# PCB-GONIO-V1.net
KiCad netlist of a schematic drawn in EAGLE
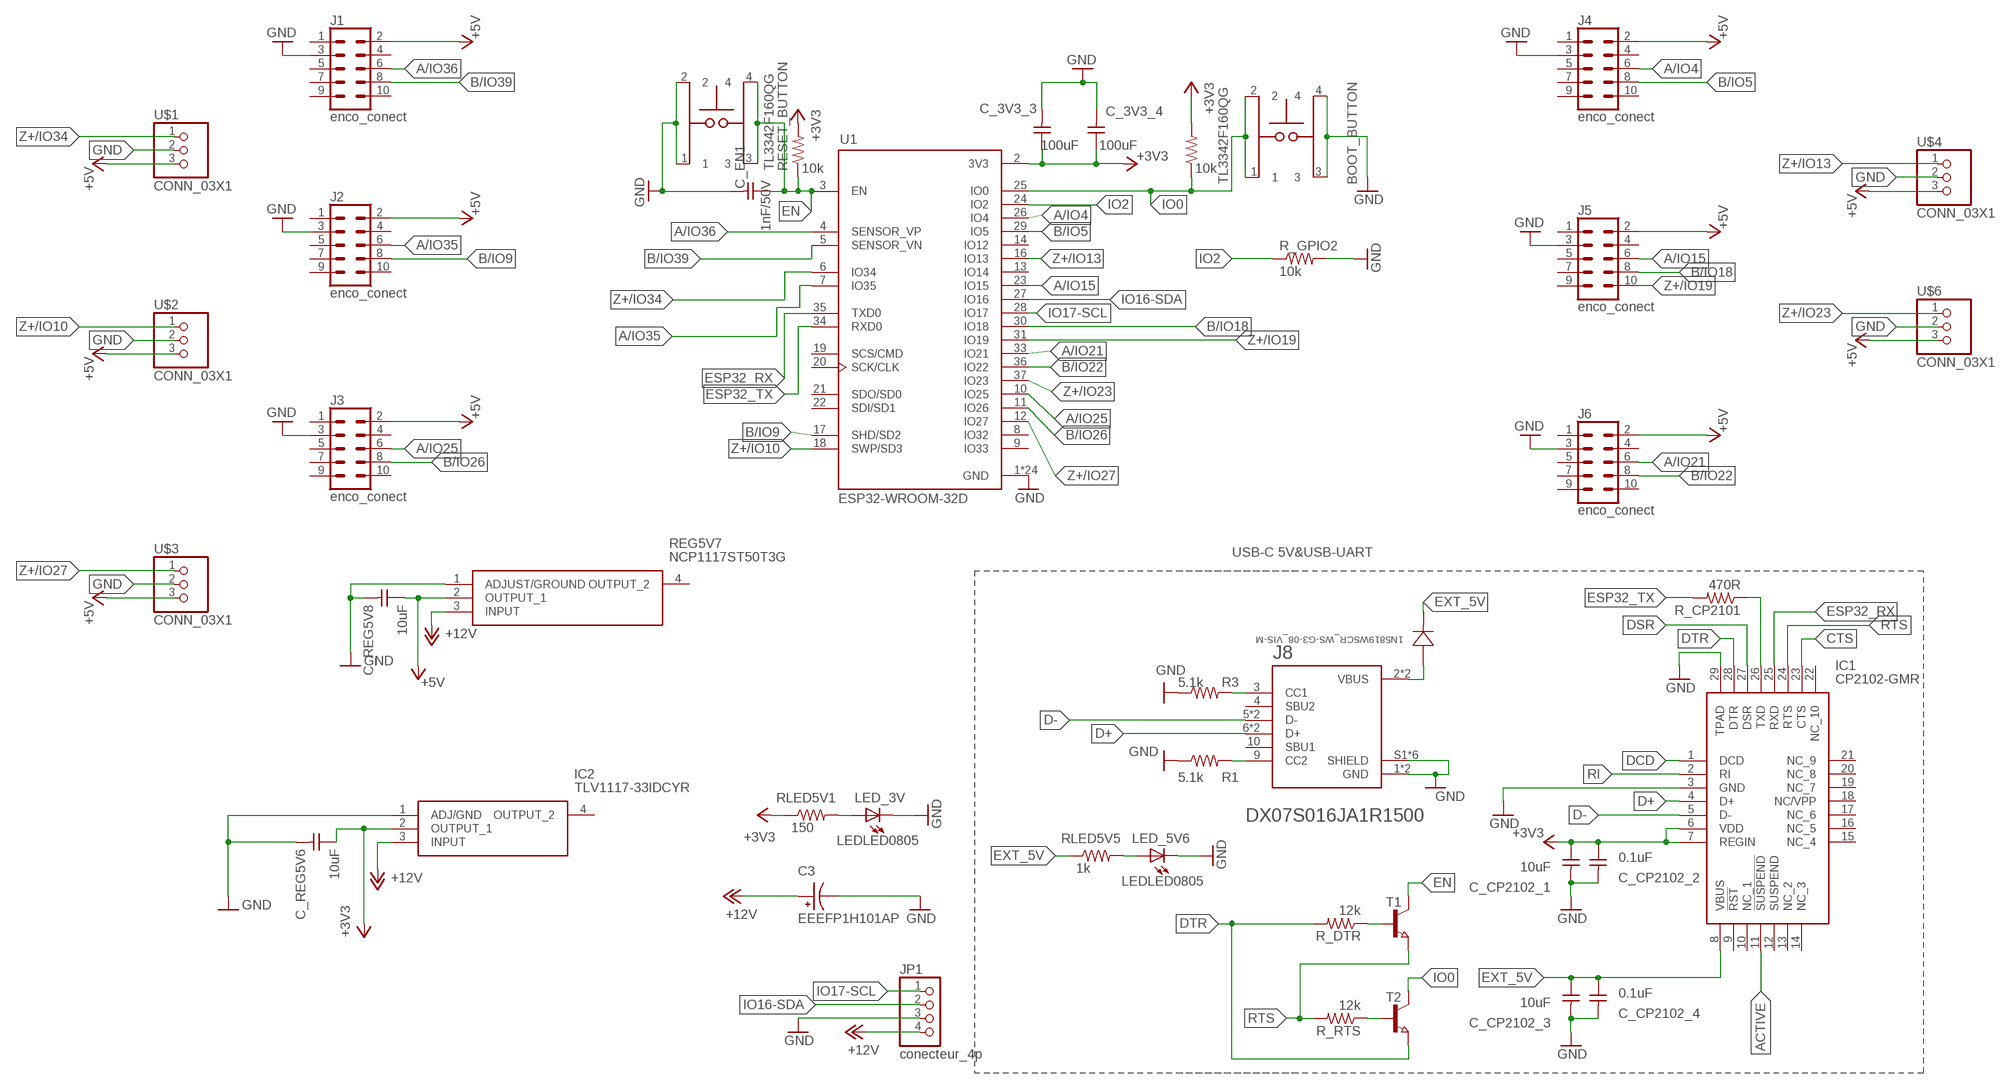
[diagram p0: schematic, sheet 1]

(export (version "E")
  (design (tool "Eeschema 10.0.6"))
  (components
    (comp (ref "BOOT_BUTTON")
      (value "TL3342F160QG")
      (footprint "eagle-import:SW_TL3342F160QG")
      (fields (field (name "MF") "E-Switch"))
      (libsource (lib "eagle-import") (part "TL3342F160QG"))
    )
    (comp (ref "C3")
      (value "EEEFP1H101AP")
      (footprint "eagle-import:CAP_EEEFP1H101AP")
      (fields (field (name "DIGIKEY_PART_NUMBER") "P19726TR-ND") (field (name "MF") "Panasonic"))
      (libsource (lib "eagle-import") (part "EEEFP1H101AP"))
    )
    (comp (ref "CR1")
      (value "1N5819WSCR_WS-G3-08_VIS-M")
      (footprint "eagle-import:CR_WS-G3-08_VIS-M")
      (fields
        (field (name "MANUFACTURER_PART_NUMBER") "1N4148WS-G3-08")
        (field (name "COPYRIGHT") "Copyright (C) 2022 Ultra Librarian. All rights reserved.")
      )
      (libsource (lib "eagle-import") (part "1N5819WSCR_WS-G3-08_VIS-M"))
    )
    (comp (ref "C_3V3_3")
      (value "100uF")
      (footprint "eagle-import:C1206FAB")
      (libsource (lib "eagle-import") (part "CAP_UNPOLARIZEDFAB"))
    )
    (comp (ref "C_3V3_4")
      (value "100uF")
      (footprint "eagle-import:C1206FAB")
      (libsource (lib "eagle-import") (part "CAP_UNPOLARIZEDFAB"))
    )
    (comp (ref "C_CP2102_1")
      (value "10uF")
      (footprint "eagle-import:C1206FAB")
      (libsource (lib "eagle-import") (part "CAP_UNPOLARIZEDFAB"))
    )
    (comp (ref "C_CP2102_2")
      (value "0.1uF")
      (footprint "eagle-import:C1206FAB")
      (libsource (lib "eagle-import") (part "CAP_UNPOLARIZEDFAB"))
    )
    (comp (ref "C_CP2102_3")
      (value "10uF")
      (footprint "eagle-import:C1206FAB")
      (libsource (lib "eagle-import") (part "CAP_UNPOLARIZEDFAB"))
    )
    (comp (ref "C_CP2102_4")
      (value "0.1uF")
      (footprint "eagle-import:C1206FAB")
      (libsource (lib "eagle-import") (part "CAP_UNPOLARIZEDFAB"))
    )
    (comp (ref "C_EN1")
      (value "1nF/50V")
      (footprint "eagle-import:C1206FAB")
      (libsource (lib "eagle-import") (part "CAP_UNPOLARIZEDFAB"))
    )
    (comp (ref "C_REG5V6")
      (value "10uF")
      (footprint "eagle-import:C1206FAB")
      (libsource (lib "eagle-import") (part "CAP_UNPOLARIZEDFAB"))
    )
    (comp (ref "C_REG5V8")
      (value "10uF")
      (footprint "eagle-import:C1206FAB")
      (libsource (lib "eagle-import") (part "CAP_UNPOLARIZEDFAB"))
    )
    (comp (ref "IC1")
      (value "CP2102-GMR")
      (footprint "eagle-import:QFN50P500X500X100-29N")
      (fields (field (name "MOUSER_PART_NUMBER") "634-CP2102-GMR"))
      (libsource (lib "eagle-import") (part "CP2102-GMR"))
    )
    (comp (ref "IC2")
      (value "TLV1117-33IDCYR")
      (footprint "eagle-import:SOT230P700X180-4N")
      (fields (field (name "MOUSER_PART_NUMBER") "595-TLV1117-33IDCYR"))
      (libsource (lib "eagle-import") (part "TLV1117-33IDCYR"))
    )
    (comp (ref "J1")
      (value "enco_conect")
      (footprint "eagle-import:2X5-SHROUDED")
      (libsource (lib "eagle-import") (part "CONN_05X2SHD"))
    )
    (comp (ref "J2")
      (value "enco_conect")
      (footprint "eagle-import:2X5-SHROUDED")
      (libsource (lib "eagle-import") (part "CONN_05X2SHD"))
    )
    (comp (ref "J3")
      (value "enco_conect")
      (footprint "eagle-import:2X5-SHROUDED")
      (libsource (lib "eagle-import") (part "CONN_05X2SHD"))
    )
    (comp (ref "J4")
      (value "enco_conect")
      (footprint "eagle-import:2X5-SHROUDED")
      (libsource (lib "eagle-import") (part "CONN_05X2SHD"))
    )
    (comp (ref "J5")
      (value "enco_conect")
      (footprint "eagle-import:2X5-SHROUDED")
      (libsource (lib "eagle-import") (part "CONN_05X2SHD"))
    )
    (comp (ref "J6")
      (value "enco_conect")
      (footprint "eagle-import:2X5-SHROUDED")
      (libsource (lib "eagle-import") (part "CONN_05X2SHD"))
    )
    (comp (ref "J8")
      (value "DX07S016JA1R1500")
      (footprint "eagle-import:JAE_DX07S016JA1R1500")
      (fields (field (name "MF") "Japan Aviation Electronics"))
      (libsource (lib "eagle-import") (part "DX07S016JA1R1500"))
    )
    (comp (ref "JP1")
      (value "conecteur_4p")
      (footprint "eagle-import:1X04")
      (libsource (lib "eagle-import") (part "PINHD-1X4"))
    )
    (comp (ref "LED_3V")
      (value "LEDLED0805")
      (footprint "eagle-import:LEDC2012X90N")
      (libsource (lib "eagle-import") (part "LEDLED0805"))
    )
    (comp (ref "LED_5V6")
      (value "LEDLED0805")
      (footprint "eagle-import:LEDC2012X90N")
      (libsource (lib "eagle-import") (part "LEDLED0805"))
    )
    (comp (ref "R1")
      (value "5.1k")
      (footprint "eagle-import:R1206W")
      (libsource (lib "eagle-import") (part "R-US_R1206W"))
    )
    (comp (ref "R3")
      (value "5.1k")
      (footprint "eagle-import:R1206W")
      (libsource (lib "eagle-import") (part "R-US_R1206W"))
    )
    (comp (ref "REG5V7")
      (value "NCP1117ST50T3G")
      (footprint "eagle-import:SOT230P700X180-4N")
      (fields (field (name "LCSC_PART") "C17314") (field (name "RS_PART_NUMBER") "8022130P"))
      (libsource (lib "eagle-import") (part "NCP1117ST50T3G"))
    )
    (comp (ref "RESET_BUTTON")
      (value "TL3342F160QG")
      (footprint "eagle-import:SW_TL3342F160QG")
      (fields (field (name "MF") "E-Switch"))
      (libsource (lib "eagle-import") (part "TL3342F160QG"))
    )
    (comp (ref "RLED5V1")
      (value "150")
      (footprint "eagle-import:R1206FAB")
      (libsource (lib "eagle-import") (part "R1206FAB"))
    )
    (comp (ref "RLED5V5")
      (value "1k")
      (footprint "eagle-import:R1206FAB")
      (libsource (lib "eagle-import") (part "R1206FAB"))
    )
    (comp (ref "R_CP2101")
      (value "470R")
      (footprint "eagle-import:R1206FAB")
      (libsource (lib "eagle-import") (part "R1206FAB"))
    )
    (comp (ref "R_DTR")
      (value "12k")
      (footprint "eagle-import:R1206FAB")
      (libsource (lib "eagle-import") (part "R1206FAB"))
    )
    (comp (ref "R_GPIO2")
      (value "10k")
      (footprint "eagle-import:R1206FAB")
      (libsource (lib "eagle-import") (part "R1206FAB"))
    )
    (comp (ref "R_PULL_UP1")
      (value "10k")
      (footprint "eagle-import:R1206FAB")
      (libsource (lib "eagle-import") (part "R1206FAB"))
    )
    (comp (ref "R_PULL_UP3")
      (value "10k")
      (footprint "eagle-import:R1206FAB")
      (libsource (lib "eagle-import") (part "R1206FAB"))
    )
    (comp (ref "R_RTS")
      (value "12k")
      (footprint "eagle-import:R1206FAB")
      (libsource (lib "eagle-import") (part "R1206FAB"))
    )
    (comp (ref "T1")
      (value "T_NPN_S8050-J3Y_CHANGJ_SOT23-BEC")
      (footprint "eagle-import:SOT23")
      (fields (field (name "LCSC_PART") "C2146"))
      (libsource (lib "eagle-import") (part "T_NPN__SOT23-BECS8050-J3Y_CHANGJ"))
    )
    (comp (ref "T2")
      (value "T_NPN_S8050-J3Y_CHANGJ_SOT23-BEC")
      (footprint "eagle-import:SOT23")
      (fields (field (name "LCSC_PART") "C2146"))
      (libsource (lib "eagle-import") (part "T_NPN__SOT23-BECS8050-J3Y_CHANGJ"))
    )
    (comp (ref "U$1")
      (value "CONN_03X1")
      (footprint "eagle-import:1X3")
      (libsource (lib "eagle-import") (part "CONN_03X1"))
    )
    (comp (ref "U$2")
      (value "CONN_03X1")
      (footprint "eagle-import:1X3")
      (libsource (lib "eagle-import") (part "CONN_03X1"))
    )
    (comp (ref "U$3")
      (value "CONN_03X1")
      (footprint "eagle-import:1X3")
      (libsource (lib "eagle-import") (part "CONN_03X1"))
    )
    (comp (ref "U$4")
      (value "CONN_03X1")
      (footprint "eagle-import:1X3")
      (libsource (lib "eagle-import") (part "CONN_03X1"))
    )
    (comp (ref "U$6")
      (value "CONN_03X1")
      (footprint "eagle-import:1X3")
      (libsource (lib "eagle-import") (part "CONN_03X1"))
    )
    (comp (ref "U1")
      (value "ESP32-WROOM-32D")
      (footprint "eagle-import:MODULE_ESP32-WROOM-32D")
      (fields (field (name "MF") "Espressif Systems"))
      (libsource (lib "eagle-import") (part "ESP32-WROOM-32D"))
    )
  )
  (nets
    (net (code "1") (name "+3V3") (class "Default")
      (node (ref "C_3V3_3") (pin "1") (pinfunction "1_1") (pintype "passive"))
      (node (ref "C_3V3_4") (pin "1") (pinfunction "1_1") (pintype "passive"))
      (node (ref "C_CP2102_1") (pin "1") (pinfunction "1_1") (pintype "passive"))
      (node (ref "C_CP2102_2") (pin "1") (pinfunction "1_1") (pintype "passive"))
      (node (ref "C_REG5V6") (pin "1") (pinfunction "1_1") (pintype "passive"))
      (node (ref "IC1") (pin "6") (pinfunction "VDD_6") (pintype "bidirectional"))
      (node (ref "IC1") (pin "7") (pinfunction "REGIN_7") (pintype "bidirectional"))
      (node (ref "IC2") (pin "2") (pinfunction "OUTPUT_1_2") (pintype "bidirectional"))
      (node (ref "RLED5V1") (pin "1") (pinfunction "1_1") (pintype "passive"))
      (node (ref "R_PULL_UP1") (pin "2") (pinfunction "2_2") (pintype "passive"))
      (node (ref "R_PULL_UP3") (pin "2") (pinfunction "2_2") (pintype "passive"))
      (node (ref "U1") (pin "2") (pinfunction "3V3_2") (pintype "power_in"))
    )
    (net (code "2") (name "+5V") (class "Default")
      (node (ref "C_REG5V8") (pin "1") (pinfunction "1_1") (pintype "passive"))
      (node (ref "J1") (pin "2") (pinfunction "2_2") (pintype "passive"))
      (node (ref "J2") (pin "2") (pinfunction "2_2") (pintype "passive"))
      (node (ref "J3") (pin "2") (pinfunction "2_2") (pintype "passive"))
      (node (ref "J4") (pin "2") (pinfunction "2_2") (pintype "passive"))
      (node (ref "J5") (pin "2") (pinfunction "2_2") (pintype "passive"))
      (node (ref "J6") (pin "2") (pinfunction "2_2") (pintype "passive"))
      (node (ref "REG5V7") (pin "2") (pinfunction "OUTPUT_1_2") (pintype "bidirectional"))
      (node (ref "U$1") (pin "3") (pinfunction "3_3") (pintype "passive"))
      (node (ref "U$2") (pin "3") (pinfunction "3_3") (pintype "passive"))
      (node (ref "U$3") (pin "3") (pinfunction "3_3") (pintype "passive"))
      (node (ref "U$4") (pin "3") (pinfunction "3_3") (pintype "passive"))
      (node (ref "U$6") (pin "3") (pinfunction "3_3") (pintype "passive"))
    )
    (net (code "3") (name "+12V") (class "Default")
      (node (ref "C3") (pin "1") (pinfunction "1_1") (pintype "passive"))
      (node (ref "IC2") (pin "3") (pinfunction "INPUT_3") (pintype "bidirectional"))
      (node (ref "JP1") (pin "4") (pinfunction "4_4") (pintype "passive"))
      (node (ref "REG5V7") (pin "3") (pinfunction "INPUT_3") (pintype "bidirectional"))
    )
    (net (code "4") (name "ACTIVE") (class "Default")
      (node (ref "IC1") (pin "11") (pinfunction "~{SUSPEND}_11") (pintype "bidirectional"))
    )
    (net (code "5") (name "A{slash}IO4") (class "Default")
      (node (ref "J4") (pin "6") (pinfunction "6_6") (pintype "passive"))
      (node (ref "U1") (pin "26") (pinfunction "IO4_26") (pintype "bidirectional"))
    )
    (net (code "6") (name "A{slash}IO15") (class "Default")
      (node (ref "J5") (pin "6") (pinfunction "6_6") (pintype "passive"))
      (node (ref "U1") (pin "23") (pinfunction "IO15_23") (pintype "bidirectional"))
    )
    (net (code "7") (name "A{slash}IO21") (class "Default")
      (node (ref "J6") (pin "6") (pinfunction "6_6") (pintype "passive"))
      (node (ref "U1") (pin "33") (pinfunction "IO21_33") (pintype "bidirectional"))
    )
    (net (code "8") (name "A{slash}IO25") (class "Default")
      (node (ref "J3") (pin "6") (pinfunction "6_6") (pintype "passive"))
      (node (ref "U1") (pin "10") (pinfunction "IO25_10") (pintype "bidirectional"))
    )
    (net (code "9") (name "A{slash}IO35") (class "Default")
      (node (ref "J2") (pin "6") (pinfunction "6_6") (pintype "passive"))
      (node (ref "U1") (pin "7") (pinfunction "IO35_7") (pintype "input"))
    )
    (net (code "10") (name "A{slash}IO36") (class "Default")
      (node (ref "J1") (pin "6") (pinfunction "6_6") (pintype "passive"))
      (node (ref "U1") (pin "4") (pinfunction "SENSOR_VP_4") (pintype "input"))
    )
    (net (code "11") (name "B{slash}IO5") (class "Default")
      (node (ref "J4") (pin "8") (pinfunction "8_8") (pintype "passive"))
      (node (ref "U1") (pin "29") (pinfunction "IO5_29") (pintype "bidirectional"))
    )
    (net (code "12") (name "B{slash}IO9") (class "Default")
      (node (ref "J2") (pin "8") (pinfunction "8_8") (pintype "passive"))
      (node (ref "U1") (pin "17") (pinfunction "SHD/SD2_17") (pintype "bidirectional"))
    )
    (net (code "13") (name "B{slash}IO18") (class "Default")
      (node (ref "J5") (pin "8") (pinfunction "8_8") (pintype "passive"))
      (node (ref "U1") (pin "30") (pinfunction "IO18_30") (pintype "bidirectional"))
    )
    (net (code "14") (name "B{slash}IO22") (class "Default")
      (node (ref "J6") (pin "8") (pinfunction "8_8") (pintype "passive"))
      (node (ref "U1") (pin "36") (pinfunction "IO22_36") (pintype "bidirectional"))
    )
    (net (code "15") (name "B{slash}IO26") (class "Default")
      (node (ref "J3") (pin "8") (pinfunction "8_8") (pintype "passive"))
      (node (ref "U1") (pin "11") (pinfunction "IO26_11") (pintype "bidirectional"))
    )
    (net (code "16") (name "B{slash}IO39") (class "Default")
      (node (ref "J1") (pin "8") (pinfunction "8_8") (pintype "passive"))
      (node (ref "U1") (pin "5") (pinfunction "SENSOR_VN_5") (pintype "input"))
    )
    (net (code "17") (name "CTS") (class "Default")
      (node (ref "IC1") (pin "23") (pinfunction "CTS_23") (pintype "bidirectional"))
    )
    (net (code "18") (name "D+") (class "Default")
      (node (ref "IC1") (pin "4") (pinfunction "D+_4") (pintype "bidirectional"))
      (node (ref "J8") (pin "6") (pinfunction "D+_6") (pintype "passive"))
      (node (ref "J8") (pin "7") (pinfunction "D+_7") (pintype "passive"))
    )
    (net (code "19") (name "D-") (class "Default")
      (node (ref "IC1") (pin "5") (pinfunction "D-_5") (pintype "bidirectional"))
      (node (ref "J8") (pin "5") (pinfunction "D-_5") (pintype "passive"))
      (node (ref "J8") (pin "8") (pinfunction "D-_8") (pintype "passive"))
    )
    (net (code "20") (name "DCD") (class "Default")
      (node (ref "IC1") (pin "1") (pinfunction "DCD_1") (pintype "bidirectional"))
    )
    (net (code "21") (name "DSR") (class "Default")
      (node (ref "IC1") (pin "27") (pinfunction "DSR_27") (pintype "bidirectional"))
    )
    (net (code "22") (name "DTR") (class "Default")
      (node (ref "IC1") (pin "28") (pinfunction "DTR_28") (pintype "bidirectional"))
      (node (ref "R_DTR") (pin "2") (pinfunction "2_2") (pintype "passive"))
      (node (ref "T2") (pin "2") (pinfunction "E_2") (pintype "passive"))
    )
    (net (code "23") (name "EN") (class "Default")
      (node (ref "C_EN1") (pin "1") (pinfunction "1_1") (pintype "passive"))
      (node (ref "RESET_BUTTON") (pin "3") (pinfunction "3_3") (pintype "passive"))
      (node (ref "RESET_BUTTON") (pin "4") (pinfunction "4_4") (pintype "passive"))
      (node (ref "R_PULL_UP1") (pin "1") (pinfunction "1_1") (pintype "passive"))
      (node (ref "T1") (pin "3") (pinfunction "C_3") (pintype "passive"))
      (node (ref "U1") (pin "3") (pinfunction "EN_3") (pintype "input"))
    )
    (net (code "24") (name "ESP32_RX") (class "Default")
      (node (ref "IC1") (pin "25") (pinfunction "RXD_25") (pintype "bidirectional"))
      (node (ref "U1") (pin "35") (pinfunction "TXD0_35") (pintype "bidirectional"))
    )
    (net (code "25") (name "ESP32_TX") (class "Default")
      (node (ref "R_CP2101") (pin "2") (pinfunction "2_2") (pintype "passive"))
      (node (ref "U1") (pin "34") (pinfunction "RXD0_34") (pintype "bidirectional"))
    )
    (net (code "26") (name "EXT_5V") (class "Default")
      (node (ref "CR1") (pin "1") (pinfunction "1_1") (pintype "passive"))
      (node (ref "C_CP2102_3") (pin "1") (pinfunction "1_1") (pintype "passive"))
      (node (ref "C_CP2102_4") (pin "1") (pinfunction "1_1") (pintype "passive"))
      (node (ref "IC1") (pin "8") (pinfunction "VBUS_8") (pintype "bidirectional"))
      (node (ref "RLED5V5") (pin "1") (pinfunction "1_1") (pintype "passive"))
    )
    (net (code "27") (name "GND") (class "Default")
      (node (ref "BOOT_BUTTON") (pin "3") (pinfunction "3_3") (pintype "passive"))
      (node (ref "BOOT_BUTTON") (pin "4") (pinfunction "4_4") (pintype "passive"))
      (node (ref "C3") (pin "2") (pinfunction "2_2") (pintype "passive"))
      (node (ref "C_3V3_3") (pin "2") (pinfunction "2_2") (pintype "passive"))
      (node (ref "C_3V3_4") (pin "2") (pinfunction "2_2") (pintype "passive"))
      (node (ref "C_CP2102_1") (pin "2") (pinfunction "2_2") (pintype "passive"))
      (node (ref "C_CP2102_2") (pin "2") (pinfunction "2_2") (pintype "passive"))
      (node (ref "C_CP2102_3") (pin "2") (pinfunction "2_2") (pintype "passive"))
      (node (ref "C_CP2102_4") (pin "2") (pinfunction "2_2") (pintype "passive"))
      (node (ref "C_EN1") (pin "2") (pinfunction "2_2") (pintype "passive"))
      (node (ref "C_REG5V6") (pin "2") (pinfunction "2_2") (pintype "passive"))
      (node (ref "C_REG5V8") (pin "2") (pinfunction "2_2") (pintype "passive"))
      (node (ref "IC1") (pin "29") (pinfunction "TPAD_29") (pintype "bidirectional"))
      (node (ref "IC1") (pin "3") (pinfunction "GND_3") (pintype "bidirectional"))
      (node (ref "IC2") (pin "1") (pinfunction "ADJ/GND_1") (pintype "bidirectional"))
      (node (ref "J1") (pin "3") (pinfunction "3_3") (pintype "passive"))
      (node (ref "J2") (pin "3") (pinfunction "3_3") (pintype "passive"))
      (node (ref "J3") (pin "3") (pinfunction "3_3") (pintype "passive"))
      (node (ref "J4") (pin "3") (pinfunction "3_3") (pintype "passive"))
      (node (ref "J5") (pin "3") (pinfunction "3_3") (pintype "passive"))
      (node (ref "J6") (pin "3") (pinfunction "3_3") (pintype "passive"))
      (node (ref "J8") (pin "1") (pinfunction "GND_1") (pintype "power_in"))
      (node (ref "J8") (pin "12") (pinfunction "GND_12") (pintype "power_in"))
      (node (ref "J8") (pin "S1") (pinfunction "SHIELD_S1") (pintype "passive"))
      (node (ref "J8") (pin "S2") (pinfunction "SHIELD_S2") (pintype "passive"))
      (node (ref "J8") (pin "S3") (pinfunction "SHIELD_S3") (pintype "passive"))
      (node (ref "J8") (pin "S4") (pinfunction "SHIELD_S4") (pintype "passive"))
      (node (ref "J8") (pin "S5") (pinfunction "SHIELD_S5") (pintype "passive"))
      (node (ref "J8") (pin "S6") (pinfunction "SHIELD_S6") (pintype "passive"))
      (node (ref "JP1") (pin "3") (pinfunction "3_3") (pintype "passive"))
      (node (ref "LED_3V") (pin "1") (pinfunction "C_1") (pintype "passive"))
      (node (ref "LED_5V6") (pin "1") (pinfunction "C_1") (pintype "passive"))
      (node (ref "R1") (pin "1") (pinfunction "1_1") (pintype "passive"))
      (node (ref "R3") (pin "1") (pinfunction "1_1") (pintype "passive"))
      (node (ref "REG5V7") (pin "1") (pinfunction "ADJUST/GROUND_1") (pintype "bidirectional"))
      (node (ref "RESET_BUTTON") (pin "1") (pinfunction "1_1") (pintype "passive"))
      (node (ref "RESET_BUTTON") (pin "2") (pinfunction "2_2") (pintype "passive"))
      (node (ref "R_GPIO2") (pin "2") (pinfunction "2_2") (pintype "passive"))
      (node (ref "U$1") (pin "2") (pinfunction "2_2") (pintype "passive"))
      (node (ref "U$2") (pin "2") (pinfunction "2_2") (pintype "passive"))
      (node (ref "U$3") (pin "2") (pinfunction "2_2") (pintype "passive"))
      (node (ref "U$4") (pin "2") (pinfunction "2_2") (pintype "passive"))
      (node (ref "U$6") (pin "2") (pinfunction "2_2") (pintype "passive"))
      (node (ref "U1") (pin "1") (pinfunction "GND_1") (pintype "power_in"))
      (node (ref "U1") (pin "15") (pinfunction "GND_15") (pintype "power_in"))
      (node (ref "U1") (pin "38") (pinfunction "GND_38") (pintype "power_in"))
      (node (ref "U1") (pin "39_1") (pinfunction "GND_39_1") (pintype "power_in"))
      (node (ref "U1") (pin "39_10") (pinfunction "GND_39_10") (pintype "power_in"))
      (node (ref "U1") (pin "39_11") (pinfunction "GND_39_11") (pintype "power_in"))
      (node (ref "U1") (pin "39_12") (pinfunction "GND_39_12") (pintype "power_in"))
      (node (ref "U1") (pin "39_13") (pinfunction "GND_39_13") (pintype "power_in"))
      (node (ref "U1") (pin "39_14") (pinfunction "GND_39_14") (pintype "power_in"))
      (node (ref "U1") (pin "39_15") (pinfunction "GND_39_15") (pintype "power_in"))
      (node (ref "U1") (pin "39_16") (pinfunction "GND_39_16") (pintype "power_in"))
      (node (ref "U1") (pin "39_17") (pinfunction "GND_39_17") (pintype "power_in"))
      (node (ref "U1") (pin "39_18") (pinfunction "GND_39_18") (pintype "power_in"))
      (node (ref "U1") (pin "39_19") (pinfunction "GND_39_19") (pintype "power_in"))
      (node (ref "U1") (pin "39_2") (pinfunction "GND_39_2") (pintype "power_in"))
      (node (ref "U1") (pin "39_20") (pinfunction "GND_39_20") (pintype "power_in"))
      (node (ref "U1") (pin "39_21") (pinfunction "GND_39_21") (pintype "power_in"))
      (node (ref "U1") (pin "39_3") (pinfunction "GND_39_3") (pintype "power_in"))
      (node (ref "U1") (pin "39_4") (pinfunction "GND_39_4") (pintype "power_in"))
      (node (ref "U1") (pin "39_5") (pinfunction "GND_39_5") (pintype "power_in"))
      (node (ref "U1") (pin "39_6") (pinfunction "GND_39_6") (pintype "power_in"))
      (node (ref "U1") (pin "39_7") (pinfunction "GND_39_7") (pintype "power_in"))
      (node (ref "U1") (pin "39_8") (pinfunction "GND_39_8") (pintype "power_in"))
      (node (ref "U1") (pin "39_9") (pinfunction "GND_39_9") (pintype "power_in"))
    )
    (net (code "28") (name "IO0") (class "Default")
      (node (ref "BOOT_BUTTON") (pin "1") (pinfunction "1_1") (pintype "passive"))
      (node (ref "BOOT_BUTTON") (pin "2") (pinfunction "2_2") (pintype "passive"))
      (node (ref "R_PULL_UP3") (pin "1") (pinfunction "1_1") (pintype "passive"))
      (node (ref "T2") (pin "3") (pinfunction "C_3") (pintype "passive"))
      (node (ref "U1") (pin "25") (pinfunction "IO0_25") (pintype "bidirectional"))
    )
    (net (code "29") (name "IO2") (class "Default")
      (node (ref "R_GPIO2") (pin "1") (pinfunction "1_1") (pintype "passive"))
      (node (ref "U1") (pin "24") (pinfunction "IO2_24") (pintype "bidirectional"))
    )
    (net (code "30") (name "IO16-SDA") (class "Default")
      (node (ref "JP1") (pin "2") (pinfunction "2_2") (pintype "passive"))
      (node (ref "U1") (pin "27") (pinfunction "IO16_27") (pintype "bidirectional"))
    )
    (net (code "31") (name "IO17-SCL") (class "Default")
      (node (ref "JP1") (pin "1") (pinfunction "1_1") (pintype "passive"))
      (node (ref "U1") (pin "28") (pinfunction "IO17_28") (pintype "bidirectional"))
    )
    (net (code "32") (name "Net-(CR1-Pad2)") (class "Default")
      (node (ref "CR1") (pin "2") (pinfunction "2_2") (pintype "passive"))
      (node (ref "J8") (pin "11") (pinfunction "VBUS_11") (pintype "power_in"))
      (node (ref "J8") (pin "2") (pinfunction "VBUS_2") (pintype "power_in"))
    )
    (net (code "33") (name "Net-(IC1-TXD)") (class "Default")
      (node (ref "IC1") (pin "26") (pinfunction "TXD_26") (pintype "bidirectional"))
      (node (ref "R_CP2101") (pin "1") (pinfunction "1_1") (pintype "passive"))
    )
    (net (code "34") (name "Net-(J8-CC1)") (class "Default")
      (node (ref "J8") (pin "3") (pinfunction "CC1_3") (pintype "passive"))
      (node (ref "R3") (pin "2") (pinfunction "2_2") (pintype "passive"))
    )
    (net (code "35") (name "Net-(J8-CC2)") (class "Default")
      (node (ref "J8") (pin "9") (pinfunction "CC2_9") (pintype "passive"))
      (node (ref "R1") (pin "2") (pinfunction "2_2") (pintype "passive"))
    )
    (net (code "36") (name "Net-(LED_3V-A)") (class "Default")
      (node (ref "LED_3V") (pin "2") (pinfunction "A_2") (pintype "passive"))
      (node (ref "RLED5V1") (pin "2") (pinfunction "2_2") (pintype "passive"))
    )
    (net (code "37") (name "Net-(LED_5V6-A)") (class "Default")
      (node (ref "LED_5V6") (pin "2") (pinfunction "A_2") (pintype "passive"))
      (node (ref "RLED5V5") (pin "2") (pinfunction "2_2") (pintype "passive"))
    )
    (net (code "38") (name "Net-(T1-B)") (class "Default")
      (node (ref "R_DTR") (pin "1") (pinfunction "1_1") (pintype "passive"))
      (node (ref "T1") (pin "1") (pinfunction "B_1") (pintype "passive"))
    )
    (net (code "39") (name "Net-(T2-B)") (class "Default")
      (node (ref "R_RTS") (pin "1") (pinfunction "1_1") (pintype "passive"))
      (node (ref "T2") (pin "1") (pinfunction "B_1") (pintype "passive"))
    )
    (net (code "40") (name "RI") (class "Default")
      (node (ref "IC1") (pin "2") (pinfunction "RI_2") (pintype "bidirectional"))
    )
    (net (code "41") (name "RTS") (class "Default")
      (node (ref "IC1") (pin "24") (pinfunction "RTS_24") (pintype "bidirectional"))
      (node (ref "R_RTS") (pin "2") (pinfunction "2_2") (pintype "passive"))
      (node (ref "T1") (pin "2") (pinfunction "E_2") (pintype "passive"))
    )
    (net (code "42") (name "Z+{slash}IO10") (class "Default")
      (node (ref "U$2") (pin "1") (pinfunction "1_1") (pintype "passive"))
      (node (ref "U1") (pin "18") (pinfunction "SWP/SD3_18") (pintype "bidirectional"))
    )
    (net (code "43") (name "Z+{slash}IO13") (class "Default")
      (node (ref "U$4") (pin "1") (pinfunction "1_1") (pintype "passive"))
      (node (ref "U1") (pin "16") (pinfunction "IO13_16") (pintype "bidirectional"))
    )
    (net (code "44") (name "Z+{slash}IO19") (class "Default")
      (node (ref "J5") (pin "10") (pinfunction "10_10") (pintype "passive"))
      (node (ref "U1") (pin "31") (pinfunction "IO19_31") (pintype "bidirectional"))
    )
    (net (code "45") (name "Z+{slash}IO23") (class "Default")
      (node (ref "U$6") (pin "1") (pinfunction "1_1") (pintype "passive"))
      (node (ref "U1") (pin "37") (pinfunction "IO23_37") (pintype "bidirectional"))
    )
    (net (code "46") (name "Z+{slash}IO27") (class "Default")
      (node (ref "U$3") (pin "1") (pinfunction "1_1") (pintype "passive"))
      (node (ref "U1") (pin "12") (pinfunction "IO27_12") (pintype "bidirectional"))
    )
    (net (code "47") (name "Z+{slash}IO34") (class "Default")
      (node (ref "U$1") (pin "1") (pinfunction "1_1") (pintype "passive"))
      (node (ref "U1") (pin "6") (pinfunction "IO34_6") (pintype "input"))
    )
    (net (code "48") (name "unconnected-(IC1-NC_1-Pad10)") (class "Default")
      (node (ref "IC1") (pin "10") (pinfunction "NC_1_10") (pintype "bidirectional"))
    )
    (net (code "49") (name "unconnected-(IC1-NC_2-Pad13)") (class "Default")
      (node (ref "IC1") (pin "13") (pinfunction "NC_2_13") (pintype "bidirectional"))
    )
    (net (code "50") (name "unconnected-(IC1-NC_3-Pad14)") (class "Default")
      (node (ref "IC1") (pin "14") (pinfunction "NC_3_14") (pintype "bidirectional"))
    )
    (net (code "51") (name "unconnected-(IC1-NC_4-Pad15)") (class "Default")
      (node (ref "IC1") (pin "15") (pinfunction "NC_4_15") (pintype "bidirectional"))
    )
    (net (code "52") (name "unconnected-(IC1-NC_5-Pad16)") (class "Default")
      (node (ref "IC1") (pin "16") (pinfunction "NC_5_16") (pintype "bidirectional"))
    )
    (net (code "53") (name "unconnected-(IC1-NC_6-Pad17)") (class "Default")
      (node (ref "IC1") (pin "17") (pinfunction "NC_6_17") (pintype "bidirectional"))
    )
    (net (code "54") (name "unconnected-(IC1-NC_7-Pad19)") (class "Default")
      (node (ref "IC1") (pin "19") (pinfunction "NC_7_19") (pintype "bidirectional"))
    )
    (net (code "55") (name "unconnected-(IC1-NC_8-Pad20)") (class "Default")
      (node (ref "IC1") (pin "20") (pinfunction "NC_8_20") (pintype "bidirectional"))
    )
    (net (code "56") (name "unconnected-(IC1-NC_9-Pad21)") (class "Default")
      (node (ref "IC1") (pin "21") (pinfunction "NC_9_21") (pintype "bidirectional"))
    )
    (net (code "57") (name "unconnected-(IC1-NC_10-Pad22)") (class "Default")
      (node (ref "IC1") (pin "22") (pinfunction "NC_10_22") (pintype "bidirectional"))
    )
    (net (code "58") (name "unconnected-(IC1-NC{slash}VPP-Pad18)") (class "Default")
      (node (ref "IC1") (pin "18") (pinfunction "NC/VPP_18") (pintype "bidirectional"))
    )
    (net (code "59") (name "unconnected-(IC1-SUSPEND-Pad12)") (class "Default")
      (node (ref "IC1") (pin "12") (pinfunction "SUSPEND_12") (pintype "bidirectional"))
    )
    (net (code "60") (name "unconnected-(IC1-~{RST}-Pad9)") (class "Default")
      (node (ref "IC1") (pin "9") (pinfunction "~{RST}_9") (pintype "bidirectional"))
    )
    (net (code "61") (name "unconnected-(IC2-OUTPUT_2-Pad4)") (class "Default")
      (node (ref "IC2") (pin "4") (pinfunction "OUTPUT_2_4") (pintype "bidirectional"))
    )
    (net (code "62") (name "unconnected-(J1-Pad1)") (class "Default")
      (node (ref "J1") (pin "1") (pinfunction "1_1") (pintype "passive"))
    )
    (net (code "63") (name "unconnected-(J1-Pad4)") (class "Default")
      (node (ref "J1") (pin "4") (pinfunction "4_4") (pintype "passive"))
    )
    (net (code "64") (name "unconnected-(J1-Pad5)") (class "Default")
      (node (ref "J1") (pin "5") (pinfunction "5_5") (pintype "passive"))
    )
    (net (code "65") (name "unconnected-(J1-Pad7)") (class "Default")
      (node (ref "J1") (pin "7") (pinfunction "7_7") (pintype "passive"))
    )
    (net (code "66") (name "unconnected-(J1-Pad9)") (class "Default")
      (node (ref "J1") (pin "9") (pinfunction "9_9") (pintype "passive"))
    )
    (net (code "67") (name "unconnected-(J1-Pad10)") (class "Default")
      (node (ref "J1") (pin "10") (pinfunction "10_10") (pintype "passive"))
    )
    (net (code "68") (name "unconnected-(J2-Pad1)") (class "Default")
      (node (ref "J2") (pin "1") (pinfunction "1_1") (pintype "passive"))
    )
    (net (code "69") (name "unconnected-(J2-Pad4)") (class "Default")
      (node (ref "J2") (pin "4") (pinfunction "4_4") (pintype "passive"))
    )
    (net (code "70") (name "unconnected-(J2-Pad5)") (class "Default")
      (node (ref "J2") (pin "5") (pinfunction "5_5") (pintype "passive"))
    )
    (net (code "71") (name "unconnected-(J2-Pad7)") (class "Default")
      (node (ref "J2") (pin "7") (pinfunction "7_7") (pintype "passive"))
    )
    (net (code "72") (name "unconnected-(J2-Pad9)") (class "Default")
      (node (ref "J2") (pin "9") (pinfunction "9_9") (pintype "passive"))
    )
    (net (code "73") (name "unconnected-(J2-Pad10)") (class "Default")
      (node (ref "J2") (pin "10") (pinfunction "10_10") (pintype "passive"))
    )
    (net (code "74") (name "unconnected-(J3-Pad1)") (class "Default")
      (node (ref "J3") (pin "1") (pinfunction "1_1") (pintype "passive"))
    )
    (net (code "75") (name "unconnected-(J3-Pad4)") (class "Default")
      (node (ref "J3") (pin "4") (pinfunction "4_4") (pintype "passive"))
    )
    (net (code "76") (name "unconnected-(J3-Pad5)") (class "Default")
      (node (ref "J3") (pin "5") (pinfunction "5_5") (pintype "passive"))
    )
    (net (code "77") (name "unconnected-(J3-Pad7)") (class "Default")
      (node (ref "J3") (pin "7") (pinfunction "7_7") (pintype "passive"))
    )
    (net (code "78") (name "unconnected-(J3-Pad9)") (class "Default")
      (node (ref "J3") (pin "9") (pinfunction "9_9") (pintype "passive"))
    )
    (net (code "79") (name "unconnected-(J3-Pad10)") (class "Default")
      (node (ref "J3") (pin "10") (pinfunction "10_10") (pintype "passive"))
    )
    (net (code "80") (name "unconnected-(J4-Pad1)") (class "Default")
      (node (ref "J4") (pin "1") (pinfunction "1_1") (pintype "passive"))
    )
    (net (code "81") (name "unconnected-(J4-Pad4)") (class "Default")
      (node (ref "J4") (pin "4") (pinfunction "4_4") (pintype "passive"))
    )
    (net (code "82") (name "unconnected-(J4-Pad5)") (class "Default")
      (node (ref "J4") (pin "5") (pinfunction "5_5") (pintype "passive"))
    )
    (net (code "83") (name "unconnected-(J4-Pad7)") (class "Default")
      (node (ref "J4") (pin "7") (pinfunction "7_7") (pintype "passive"))
    )
    (net (code "84") (name "unconnected-(J4-Pad9)") (class "Default")
      (node (ref "J4") (pin "9") (pinfunction "9_9") (pintype "passive"))
    )
    (net (code "85") (name "unconnected-(J4-Pad10)") (class "Default")
      (node (ref "J4") (pin "10") (pinfunction "10_10") (pintype "passive"))
    )
    (net (code "86") (name "unconnected-(J5-Pad1)") (class "Default")
      (node (ref "J5") (pin "1") (pinfunction "1_1") (pintype "passive"))
    )
    (net (code "87") (name "unconnected-(J5-Pad4)") (class "Default")
      (node (ref "J5") (pin "4") (pinfunction "4_4") (pintype "passive"))
    )
    (net (code "88") (name "unconnected-(J5-Pad5)") (class "Default")
      (node (ref "J5") (pin "5") (pinfunction "5_5") (pintype "passive"))
    )
    (net (code "89") (name "unconnected-(J5-Pad7)") (class "Default")
      (node (ref "J5") (pin "7") (pinfunction "7_7") (pintype "passive"))
    )
    (net (code "90") (name "unconnected-(J5-Pad9)") (class "Default")
      (node (ref "J5") (pin "9") (pinfunction "9_9") (pintype "passive"))
    )
    (net (code "91") (name "unconnected-(J6-Pad1)") (class "Default")
      (node (ref "J6") (pin "1") (pinfunction "1_1") (pintype "passive"))
    )
    (net (code "92") (name "unconnected-(J6-Pad4)") (class "Default")
      (node (ref "J6") (pin "4") (pinfunction "4_4") (pintype "passive"))
    )
    (net (code "93") (name "unconnected-(J6-Pad5)") (class "Default")
      (node (ref "J6") (pin "5") (pinfunction "5_5") (pintype "passive"))
    )
    (net (code "94") (name "unconnected-(J6-Pad7)") (class "Default")
      (node (ref "J6") (pin "7") (pinfunction "7_7") (pintype "passive"))
    )
    (net (code "95") (name "unconnected-(J6-Pad9)") (class "Default")
      (node (ref "J6") (pin "9") (pinfunction "9_9") (pintype "passive"))
    )
    (net (code "96") (name "unconnected-(J6-Pad10)") (class "Default")
      (node (ref "J6") (pin "10") (pinfunction "10_10") (pintype "passive"))
    )
    (net (code "97") (name "unconnected-(J8-SBU1-Pad10)") (class "Default")
      (node (ref "J8") (pin "10") (pinfunction "SBU1_10") (pintype "passive"))
    )
    (net (code "98") (name "unconnected-(J8-SBU2-Pad4)") (class "Default")
      (node (ref "J8") (pin "4") (pinfunction "SBU2_4") (pintype "passive"))
    )
    (net (code "99") (name "unconnected-(REG5V7-OUTPUT_2-Pad4)") (class "Default")
      (node (ref "REG5V7") (pin "4") (pinfunction "OUTPUT_2_4") (pintype "bidirectional"))
    )
    (net (code "100") (name "unconnected-(U1-IO12-Pad14)") (class "Default")
      (node (ref "U1") (pin "14") (pinfunction "IO12_14") (pintype "bidirectional"))
    )
    (net (code "101") (name "unconnected-(U1-IO14-Pad13)") (class "Default")
      (node (ref "U1") (pin "13") (pinfunction "IO14_13") (pintype "bidirectional"))
    )
    (net (code "102") (name "unconnected-(U1-IO32-Pad8)") (class "Default")
      (node (ref "U1") (pin "8") (pinfunction "IO32_8") (pintype "bidirectional"))
    )
    (net (code "103") (name "unconnected-(U1-IO33-Pad9)") (class "Default")
      (node (ref "U1") (pin "9") (pinfunction "IO33_9") (pintype "bidirectional"))
    )
    (net (code "104") (name "unconnected-(U1-SCK{slash}CLK-Pad20)") (class "Default")
      (node (ref "U1") (pin "20") (pinfunction "SCK/CLK_20") (pintype "bidirectional"))
    )
    (net (code "105") (name "unconnected-(U1-SCS{slash}CMD-Pad19)") (class "Default")
      (node (ref "U1") (pin "19") (pinfunction "SCS/CMD_19") (pintype "bidirectional"))
    )
    (net (code "106") (name "unconnected-(U1-SDI{slash}SD1-Pad22)") (class "Default")
      (node (ref "U1") (pin "22") (pinfunction "SDI/SD1_22") (pintype "bidirectional"))
    )
    (net (code "107") (name "unconnected-(U1-SDO{slash}SD0-Pad21)") (class "Default")
      (node (ref "U1") (pin "21") (pinfunction "SDO/SD0_21") (pintype "bidirectional"))
    )
  )
)
